# Sensor_Conjunto.net
KiCad netlist of a schematic drawn in Altium Designer
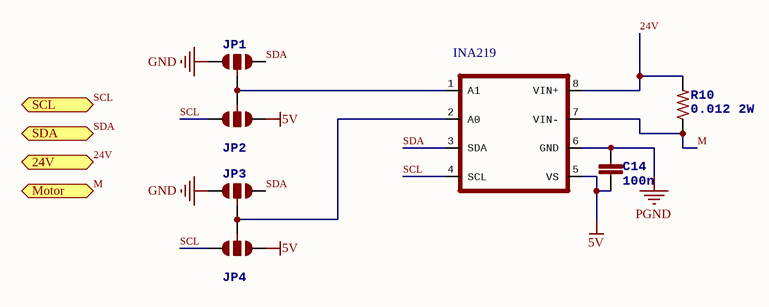
[diagram p0: Sensor_Conjunto.SchDoc]

(export (version "E")
  (design (tool "Eeschema 10.0.6"))
  (components
    (comp (ref "C14")
      (value "100n")
      (footprint "SparkFun-Passives:0805")
      (libsource (lib "SparkFun-Passives") (part "CAP0805"))
    )
    (comp (ref "IC1") (value "INA219") (footprint "SO08") (libsource (lib "INA219") (part "INA219-SO8D")))
    (comp (ref "JP1")
      (value "JUMPER-PAD-3-NOYES_SILK")
      (footprint "PAD-JUMPER-3-NO_YES_SILK")
      (libsource (lib "") (part "JUMPER-PAD-3-NOYES_SILK_1"))
    )
    (comp (ref "JP2")
      (value "JUMPER-PAD-3-NOYES_SILK")
      (footprint "PAD-JUMPER-3-NO_YES_SILK")
      (libsource (lib "SparkFun-Passives") (part "JUMPER-PAD-3-NOYES_SILK"))
    )
    (comp (ref "JP3")
      (value "JUMPER-PAD-3-NOYES_SILK")
      (footprint "PAD-JUMPER-3-NO_YES_SILK")
      (libsource (lib "") (part "JUMPER-PAD-3-NOYES_SILK_1"))
    )
    (comp (ref "JP4")
      (value "JUMPER-PAD-3-NOYES_SILK")
      (footprint "PAD-JUMPER-3-NO_YES_SILK")
      (libsource (lib "SparkFun-Passives") (part "JUMPER-PAD-3-NOYES_SILK"))
    )
    (comp (ref "R10")
      (value "0.012 2W")
      (footprint "R2512")
      (libsource (lib "SparkFun-Resistors") (part "RESISTOR2512"))
    )
  )
  (nets
    (net (code "1") (name "/24V") (class "Default")
      (node (ref "IC1") (pin "8") (pinfunction "VIN+_8") (pintype "passive"))
      (node (ref "R10") (pin "2") (pinfunction "2_2") (pintype "passive"))
    )
    (net (code "2") (name "/M") (class "Default")
      (node (ref "IC1") (pin "7") (pinfunction "VIN-_7") (pintype "passive"))
      (node (ref "R10") (pin "1") (pinfunction "1_1") (pintype "passive"))
    )
    (net (code "3") (name "/SCL") (class "Default")
      (node (ref "IC1") (pin "4") (pinfunction "SCL_4") (pintype "passive"))
      (node (ref "JP2") (pin "3") (pinfunction "3_3") (pintype "passive"))
      (node (ref "JP4") (pin "3") (pinfunction "3_3") (pintype "passive"))
    )
    (net (code "4") (name "/SDA") (class "Default")
      (node (ref "IC1") (pin "3") (pinfunction "SDA_3") (pintype "passive"))
      (node (ref "JP1") (pin "3") (pinfunction "3_3") (pintype "passive"))
      (node (ref "JP3") (pin "3") (pinfunction "3_3") (pintype "passive"))
    )
    (net (code "5") (name "5V") (class "Default")
      (node (ref "C14") (pin "1") (pinfunction "1_1") (pintype "passive"))
      (node (ref "IC1") (pin "5") (pinfunction "VS_5") (pintype "power_in"))
      (node (ref "JP2") (pin "1") (pinfunction "1_1") (pintype "passive"))
      (node (ref "JP4") (pin "1") (pinfunction "1_1") (pintype "passive"))
    )
    (net (code "6") (name "GND") (class "Default")
      (node (ref "JP1") (pin "1") (pinfunction "1_1") (pintype "passive"))
      (node (ref "JP3") (pin "1") (pinfunction "1_1") (pintype "passive"))
    )
    (net (code "7") (name "Net-(IC1-A0)") (class "Default")
      (node (ref "IC1") (pin "2") (pinfunction "A0_2") (pintype "passive"))
      (node (ref "JP3") (pin "2") (pinfunction "2_2") (pintype "passive"))
      (node (ref "JP4") (pin "2") (pinfunction "2_2") (pintype "passive"))
    )
    (net (code "8") (name "Net-(IC1-A1)") (class "Default")
      (node (ref "IC1") (pin "1") (pinfunction "A1_1") (pintype "passive"))
      (node (ref "JP1") (pin "2") (pinfunction "2_2") (pintype "passive"))
      (node (ref "JP2") (pin "2") (pinfunction "2_2") (pintype "passive"))
    )
    (net (code "9") (name "PGND") (class "Default")
      (node (ref "C14") (pin "2") (pinfunction "2_2") (pintype "passive"))
      (node (ref "IC1") (pin "6") (pinfunction "GND_6") (pintype "power_in"))
    )
  )
)
